# VFD-IV-25-5x7x2_t2.net
KiCad netlist of a schematic drawn in EAGLE
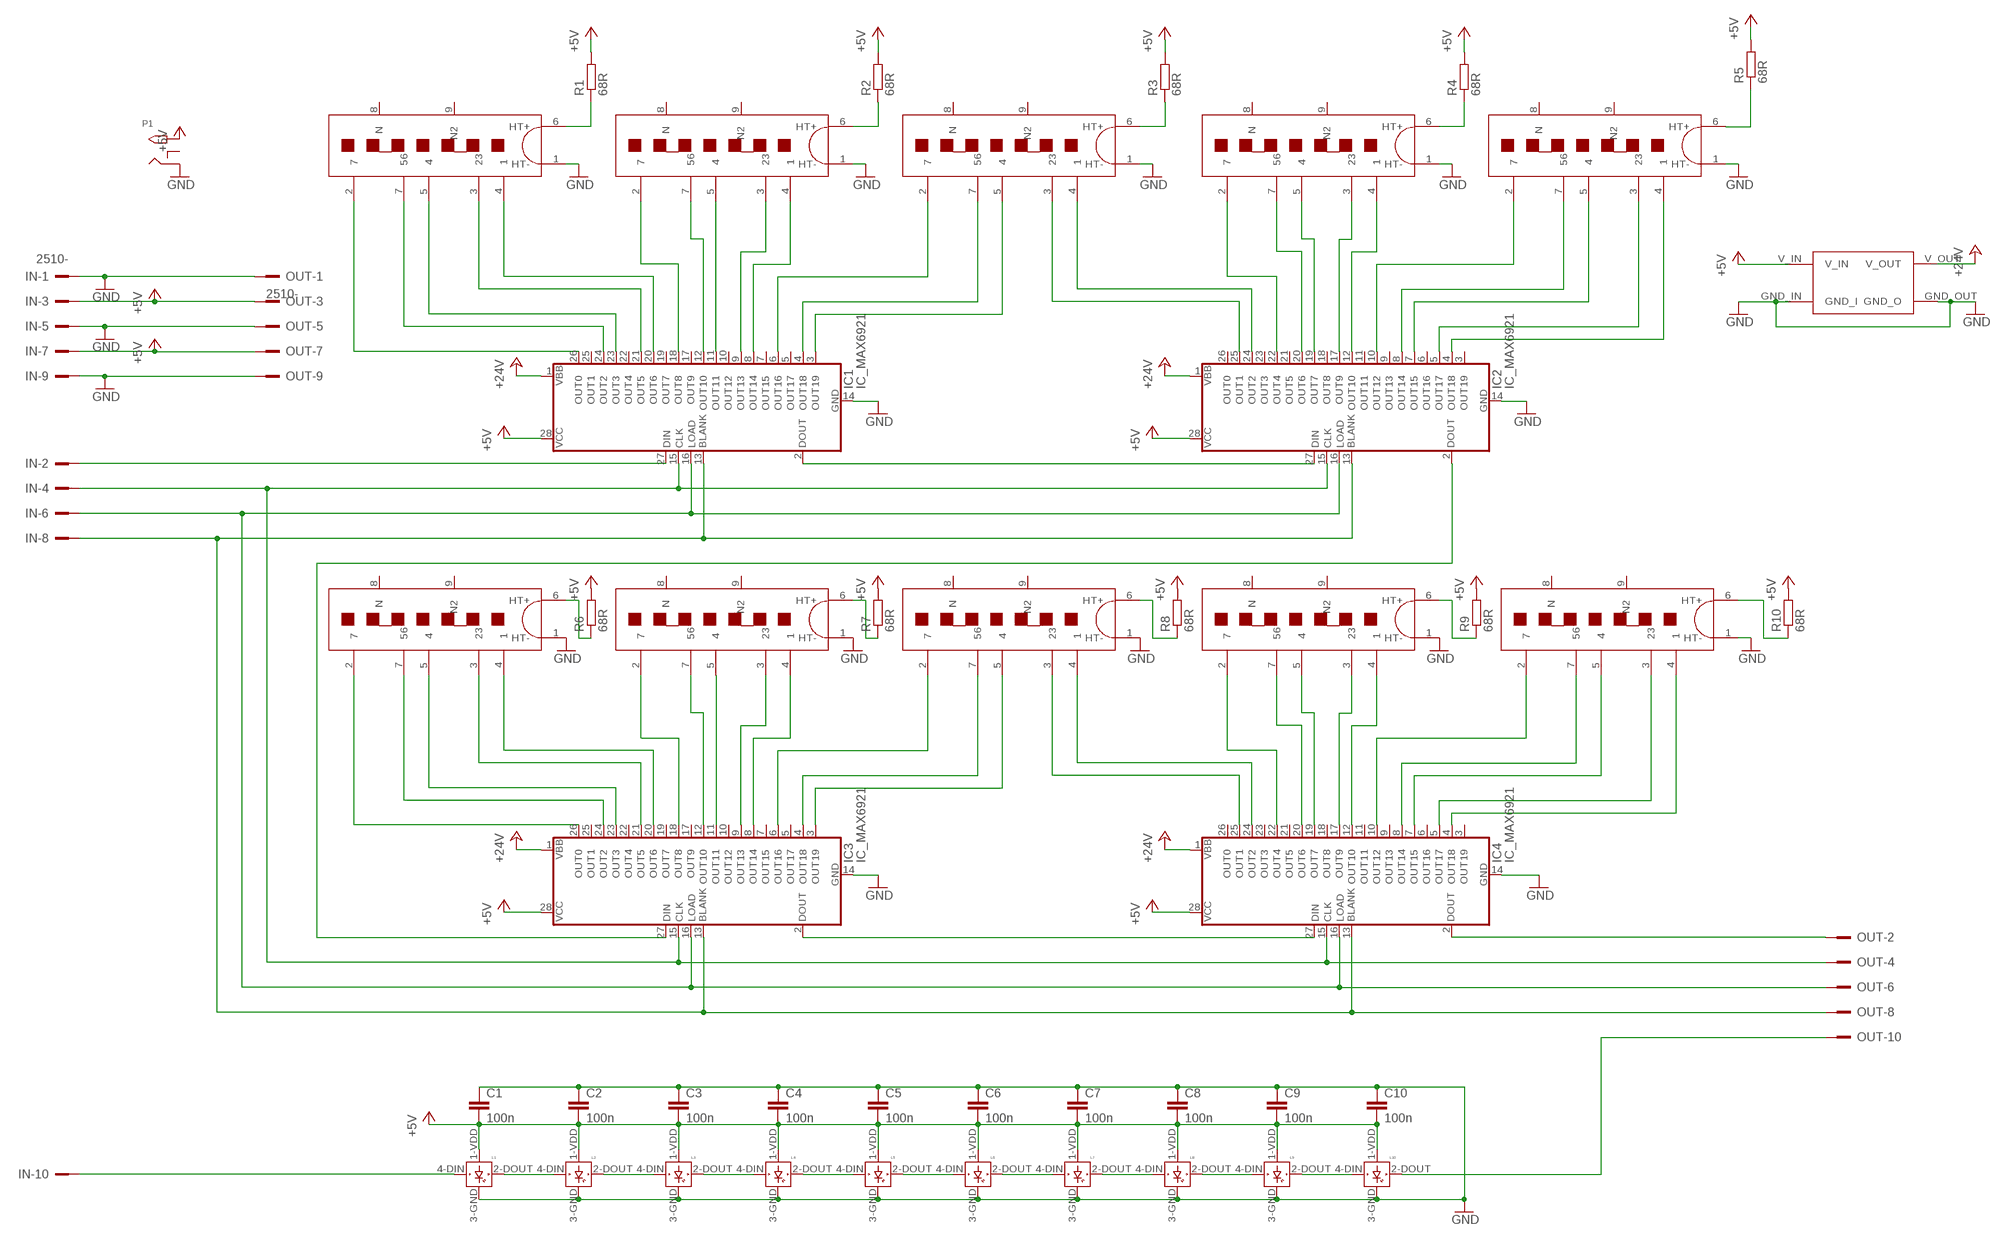
[diagram p0: schematic, sheet 1]

(export (version "E")
  (design (tool "Eeschema 10.0.6"))
  (components
    (comp (ref "1")
      (value "IV-25_DISP_T3")
      (footprint "eagle-import:IV-25")
      (libsource (lib "eagle-import") (part "IV-25_DISP_T3"))
    )
    (comp (ref "2")
      (value "IV-25_DISP_T3")
      (footprint "eagle-import:IV-25")
      (libsource (lib "eagle-import") (part "IV-25_DISP_T3"))
    )
    (comp (ref "3")
      (value "IV-25_DISP_T3")
      (footprint "eagle-import:IV-25")
      (libsource (lib "eagle-import") (part "IV-25_DISP_T3"))
    )
    (comp (ref "4")
      (value "IV-25_DISP_T3")
      (footprint "eagle-import:IV-25")
      (libsource (lib "eagle-import") (part "IV-25_DISP_T3"))
    )
    (comp (ref "5")
      (value "IV-25_DISP_T3")
      (footprint "eagle-import:IV-25")
      (libsource (lib "eagle-import") (part "IV-25_DISP_T3"))
    )
    (comp (ref "6")
      (value "IV-25_DISP_T3")
      (footprint "eagle-import:IV-25")
      (libsource (lib "eagle-import") (part "IV-25_DISP_T3"))
    )
    (comp (ref "7")
      (value "IV-25_DISP_T3")
      (footprint "eagle-import:IV-25")
      (libsource (lib "eagle-import") (part "IV-25_DISP_T3"))
    )
    (comp (ref "8")
      (value "IV-25_DISP_T3")
      (footprint "eagle-import:IV-25")
      (libsource (lib "eagle-import") (part "IV-25_DISP_T3"))
    )
    (comp (ref "9")
      (value "IV-25_DISP_T3")
      (footprint "eagle-import:IV-25")
      (libsource (lib "eagle-import") (part "IV-25_DISP_T3"))
    )
    (comp (ref "10")
      (value "IV-25_DISP_T3")
      (footprint "eagle-import:IV-25")
      (libsource (lib "eagle-import") (part "IV-25_DISP_T3"))
    )
    (comp (ref "C1")
      (value "100n")
      (footprint "eagle-import:C050-025X075")
      (libsource (lib "eagle-import") (part "C-EU050-025X075"))
    )
    (comp (ref "C2")
      (value "100n")
      (footprint "eagle-import:C050-025X075")
      (libsource (lib "eagle-import") (part "C-EU050-025X075"))
    )
    (comp (ref "C3")
      (value "100n")
      (footprint "eagle-import:C050-025X075")
      (libsource (lib "eagle-import") (part "C-EU050-025X075"))
    )
    (comp (ref "C4")
      (value "100n")
      (footprint "eagle-import:C050-025X075")
      (libsource (lib "eagle-import") (part "C-EU050-025X075"))
    )
    (comp (ref "C5")
      (value "100n")
      (footprint "eagle-import:C050-025X075")
      (libsource (lib "eagle-import") (part "C-EU050-025X075"))
    )
    (comp (ref "C6")
      (value "100n")
      (footprint "eagle-import:C050-025X075")
      (libsource (lib "eagle-import") (part "C-EU050-025X075"))
    )
    (comp (ref "C7")
      (value "100n")
      (footprint "eagle-import:C050-025X075")
      (libsource (lib "eagle-import") (part "C-EU050-025X075"))
    )
    (comp (ref "C8")
      (value "100n")
      (footprint "eagle-import:C050-025X075")
      (libsource (lib "eagle-import") (part "C-EU050-025X075"))
    )
    (comp (ref "C9")
      (value "100n")
      (footprint "eagle-import:C050-025X075")
      (libsource (lib "eagle-import") (part "C-EU050-025X075"))
    )
    (comp (ref "C10")
      (value "100n")
      (footprint "eagle-import:C050-025X075")
      (libsource (lib "eagle-import") (part "C-EU050-025X075"))
    )
    (comp (ref "IC1")
      (value "IC_MAX6921")
      (footprint "eagle-import:S28")
      (libsource (lib "eagle-import") (part "IC_MAX6921"))
    )
    (comp (ref "IC2")
      (value "IC_MAX6921")
      (footprint "eagle-import:S28")
      (libsource (lib "eagle-import") (part "IC_MAX6921"))
    )
    (comp (ref "IC3")
      (value "IC_MAX6921")
      (footprint "eagle-import:S28")
      (libsource (lib "eagle-import") (part "IC_MAX6921"))
    )
    (comp (ref "IC4")
      (value "IC_MAX6921")
      (footprint "eagle-import:S28")
      (libsource (lib "eagle-import") (part "IC_MAX6921"))
    )
    (comp (ref "IN")
      (value "2510-")
      (footprint "eagle-import:PAK100_2500-10")
      (fields (field (name "MF") "3M") (field (name "MPN") "2510-6002UB"))
      (libsource (lib "eagle-import") (part "2510-"))
    )
    (comp (ref "L1")
      (value "WS2812B")
      (footprint "eagle-import:WS2812B")
      (libsource (lib "eagle-import") (part "WS2812B"))
    )
    (comp (ref "L2")
      (value "WS2812B")
      (footprint "eagle-import:WS2812B")
      (libsource (lib "eagle-import") (part "WS2812B"))
    )
    (comp (ref "L3")
      (value "WS2812B")
      (footprint "eagle-import:WS2812B")
      (libsource (lib "eagle-import") (part "WS2812B"))
    )
    (comp (ref "L4")
      (value "WS2812B")
      (footprint "eagle-import:WS2812B")
      (libsource (lib "eagle-import") (part "WS2812B"))
    )
    (comp (ref "L5")
      (value "WS2812B")
      (footprint "eagle-import:WS2812B")
      (libsource (lib "eagle-import") (part "WS2812B"))
    )
    (comp (ref "L6")
      (value "WS2812B")
      (footprint "eagle-import:WS2812B")
      (libsource (lib "eagle-import") (part "WS2812B"))
    )
    (comp (ref "L7")
      (value "WS2812B")
      (footprint "eagle-import:WS2812B")
      (libsource (lib "eagle-import") (part "WS2812B"))
    )
    (comp (ref "L8")
      (value "WS2812B")
      (footprint "eagle-import:WS2812B")
      (libsource (lib "eagle-import") (part "WS2812B"))
    )
    (comp (ref "L9")
      (value "WS2812B")
      (footprint "eagle-import:WS2812B")
      (libsource (lib "eagle-import") (part "WS2812B"))
    )
    (comp (ref "L10")
      (value "WS2812B")
      (footprint "eagle-import:WS2812B")
      (libsource (lib "eagle-import") (part "WS2812B"))
    )
    (comp (ref "OUT")
      (value "2510-")
      (footprint "eagle-import:PAK100_2500-10")
      (fields (field (name "MF") "3M") (field (name "MPN") "2510-6002UB"))
      (libsource (lib "eagle-import") (part "2510-"))
    )
    (comp (ref "P1")
      (value "2.1MMJACKTHM")
      (footprint "eagle-import:PJ-102A")
      (libsource (lib "eagle-import") (part "2.1MMJACKTHM"))
    )
    (comp (ref "R1")
      (value "68R")
      (footprint "eagle-import:0207_10")
      (libsource (lib "eagle-import") (part "R-EU_0207/10"))
    )
    (comp (ref "R2")
      (value "68R")
      (footprint "eagle-import:0207_10")
      (libsource (lib "eagle-import") (part "R-EU_0207/10"))
    )
    (comp (ref "R3")
      (value "68R")
      (footprint "eagle-import:0207_10")
      (libsource (lib "eagle-import") (part "R-EU_0207/10"))
    )
    (comp (ref "R4")
      (value "68R")
      (footprint "eagle-import:0207_10")
      (libsource (lib "eagle-import") (part "R-EU_0207/10"))
    )
    (comp (ref "R5")
      (value "68R")
      (footprint "eagle-import:0207_10")
      (libsource (lib "eagle-import") (part "R-EU_0207/10"))
    )
    (comp (ref "R6")
      (value "68R")
      (footprint "eagle-import:0207_10")
      (libsource (lib "eagle-import") (part "R-EU_0207/10"))
    )
    (comp (ref "R7")
      (value "68R")
      (footprint "eagle-import:0207_10")
      (libsource (lib "eagle-import") (part "R-EU_0207/10"))
    )
    (comp (ref "R8")
      (value "68R")
      (footprint "eagle-import:0207_10")
      (libsource (lib "eagle-import") (part "R-EU_0207/10"))
    )
    (comp (ref "R9")
      (value "68R")
      (footprint "eagle-import:0207_10")
      (libsource (lib "eagle-import") (part "R-EU_0207/10"))
    )
    (comp (ref "R10")
      (value "68R")
      (footprint "eagle-import:0207_10")
      (libsource (lib "eagle-import") (part "R-EU_0207/10"))
    )
    (comp (ref "U$11")
      (value "STEP_UP_MODULE")
      (footprint "eagle-import:STEP_UP_MODULE")
      (libsource (lib "eagle-import") (part "STEP_UP_MODULE"))
    )
  )
  (nets
    (net (code "1") (name "+5V") (class "Default")
      (node (ref "C1") (pin "2") (pinfunction "2_2") (pintype "passive"))
      (node (ref "C10") (pin "2") (pinfunction "2_2") (pintype "passive"))
      (node (ref "C2") (pin "2") (pinfunction "2_2") (pintype "passive"))
      (node (ref "C3") (pin "2") (pinfunction "2_2") (pintype "passive"))
      (node (ref "C4") (pin "2") (pinfunction "2_2") (pintype "passive"))
      (node (ref "C5") (pin "2") (pinfunction "2_2") (pintype "passive"))
      (node (ref "C6") (pin "2") (pinfunction "2_2") (pintype "passive"))
      (node (ref "C7") (pin "2") (pinfunction "2_2") (pintype "passive"))
      (node (ref "C8") (pin "2") (pinfunction "2_2") (pintype "passive"))
      (node (ref "C9") (pin "2") (pinfunction "2_2") (pintype "passive"))
      (node (ref "IC1") (pin "28") (pinfunction "VCC_28") (pintype "power_in"))
      (node (ref "IC2") (pin "28") (pinfunction "VCC_28") (pintype "power_in"))
      (node (ref "IC3") (pin "28") (pinfunction "VCC_28") (pintype "power_in"))
      (node (ref "IC4") (pin "28") (pinfunction "VCC_28") (pintype "power_in"))
      (node (ref "IN") (pin "3") (pinfunction "KL_3") (pintype "passive"))
      (node (ref "IN") (pin "7") (pinfunction "KL_7") (pintype "passive"))
      (node (ref "L1") (pin "1-VDD") (pinfunction "VDD_1-VDD") (pintype "bidirectional"))
      (node (ref "L10") (pin "1-VDD") (pinfunction "VDD_1-VDD") (pintype "bidirectional"))
      (node (ref "L2") (pin "1-VDD") (pinfunction "VDD_1-VDD") (pintype "bidirectional"))
      (node (ref "L3") (pin "1-VDD") (pinfunction "VDD_1-VDD") (pintype "bidirectional"))
      (node (ref "L4") (pin "1-VDD") (pinfunction "VDD_1-VDD") (pintype "bidirectional"))
      (node (ref "L5") (pin "1-VDD") (pinfunction "VDD_1-VDD") (pintype "bidirectional"))
      (node (ref "L6") (pin "1-VDD") (pinfunction "VDD_1-VDD") (pintype "bidirectional"))
      (node (ref "L7") (pin "1-VDD") (pinfunction "VDD_1-VDD") (pintype "bidirectional"))
      (node (ref "L8") (pin "1-VDD") (pinfunction "VDD_1-VDD") (pintype "bidirectional"))
      (node (ref "L9") (pin "1-VDD") (pinfunction "VDD_1-VDD") (pintype "bidirectional"))
      (node (ref "OUT") (pin "3") (pinfunction "KL_3") (pintype "passive"))
      (node (ref "OUT") (pin "7") (pinfunction "KL_7") (pintype "passive"))
      (node (ref "P1") (pin "TIP") (pinfunction "TIP_TIP") (pintype "bidirectional"))
      (node (ref "R1") (pin "2") (pinfunction "2_2") (pintype "passive"))
      (node (ref "R10") (pin "2") (pinfunction "2_2") (pintype "passive"))
      (node (ref "R2") (pin "2") (pinfunction "2_2") (pintype "passive"))
      (node (ref "R3") (pin "2") (pinfunction "2_2") (pintype "passive"))
      (node (ref "R4") (pin "2") (pinfunction "2_2") (pintype "passive"))
      (node (ref "R5") (pin "2") (pinfunction "2_2") (pintype "passive"))
      (node (ref "R6") (pin "2") (pinfunction "2_2") (pintype "passive"))
      (node (ref "R7") (pin "2") (pinfunction "2_2") (pintype "passive"))
      (node (ref "R8") (pin "2") (pinfunction "2_2") (pintype "passive"))
      (node (ref "R9") (pin "2") (pinfunction "2_2") (pintype "passive"))
      (node (ref "U$11") (pin "V_IN") (pinfunction "V_IN_V_IN") (pintype "power_in"))
    )
    (net (code "2") (name "+24V") (class "Default")
      (node (ref "IC1") (pin "1") (pinfunction "VBB_1") (pintype "power_in"))
      (node (ref "IC2") (pin "1") (pinfunction "VBB_1") (pintype "power_in"))
      (node (ref "IC3") (pin "1") (pinfunction "VBB_1") (pintype "power_in"))
      (node (ref "IC4") (pin "1") (pinfunction "VBB_1") (pintype "power_in"))
      (node (ref "U$11") (pin "V_OUT") (pinfunction "V_OUT_V_OUT") (pintype "power_in"))
    )
    (net (code "3") (name "GND") (class "Default")
      (node (ref "1") (pin "1") (pinfunction "HT-_1") (pintype "bidirectional"))
      (node (ref "10") (pin "1") (pinfunction "HT-_1") (pintype "bidirectional"))
      (node (ref "2") (pin "1") (pinfunction "HT-_1") (pintype "bidirectional"))
      (node (ref "3") (pin "1") (pinfunction "HT-_1") (pintype "bidirectional"))
      (node (ref "4") (pin "1") (pinfunction "HT-_1") (pintype "bidirectional"))
      (node (ref "5") (pin "1") (pinfunction "HT-_1") (pintype "bidirectional"))
      (node (ref "6") (pin "1") (pinfunction "HT-_1") (pintype "bidirectional"))
      (node (ref "7") (pin "1") (pinfunction "HT-_1") (pintype "bidirectional"))
      (node (ref "8") (pin "1") (pinfunction "HT-_1") (pintype "bidirectional"))
      (node (ref "9") (pin "1") (pinfunction "HT-_1") (pintype "bidirectional"))
      (node (ref "C1") (pin "1") (pinfunction "1_1") (pintype "passive"))
      (node (ref "C10") (pin "1") (pinfunction "1_1") (pintype "passive"))
      (node (ref "C2") (pin "1") (pinfunction "1_1") (pintype "passive"))
      (node (ref "C3") (pin "1") (pinfunction "1_1") (pintype "passive"))
      (node (ref "C4") (pin "1") (pinfunction "1_1") (pintype "passive"))
      (node (ref "C5") (pin "1") (pinfunction "1_1") (pintype "passive"))
      (node (ref "C6") (pin "1") (pinfunction "1_1") (pintype "passive"))
      (node (ref "C7") (pin "1") (pinfunction "1_1") (pintype "passive"))
      (node (ref "C8") (pin "1") (pinfunction "1_1") (pintype "passive"))
      (node (ref "C9") (pin "1") (pinfunction "1_1") (pintype "passive"))
      (node (ref "IC1") (pin "14") (pinfunction "GND_14") (pintype "power_in"))
      (node (ref "IC2") (pin "14") (pinfunction "GND_14") (pintype "power_in"))
      (node (ref "IC3") (pin "14") (pinfunction "GND_14") (pintype "power_in"))
      (node (ref "IC4") (pin "14") (pinfunction "GND_14") (pintype "power_in"))
      (node (ref "IN") (pin "1") (pinfunction "KL_1") (pintype "passive"))
      (node (ref "IN") (pin "5") (pinfunction "KL_5") (pintype "passive"))
      (node (ref "IN") (pin "9") (pinfunction "KL_9") (pintype "passive"))
      (node (ref "L1") (pin "3-GND") (pinfunction "GND_3-GND") (pintype "bidirectional"))
      (node (ref "L10") (pin "3-GND") (pinfunction "GND_3-GND") (pintype "bidirectional"))
      (node (ref "L2") (pin "3-GND") (pinfunction "GND_3-GND") (pintype "bidirectional"))
      (node (ref "L3") (pin "3-GND") (pinfunction "GND_3-GND") (pintype "bidirectional"))
      (node (ref "L4") (pin "3-GND") (pinfunction "GND_3-GND") (pintype "bidirectional"))
      (node (ref "L5") (pin "3-GND") (pinfunction "GND_3-GND") (pintype "bidirectional"))
      (node (ref "L6") (pin "3-GND") (pinfunction "GND_3-GND") (pintype "bidirectional"))
      (node (ref "L7") (pin "3-GND") (pinfunction "GND_3-GND") (pintype "bidirectional"))
      (node (ref "L8") (pin "3-GND") (pinfunction "GND_3-GND") (pintype "bidirectional"))
      (node (ref "L9") (pin "3-GND") (pinfunction "GND_3-GND") (pintype "bidirectional"))
      (node (ref "OUT") (pin "1") (pinfunction "KL_1") (pintype "passive"))
      (node (ref "OUT") (pin "5") (pinfunction "KL_5") (pintype "passive"))
      (node (ref "OUT") (pin "9") (pinfunction "KL_9") (pintype "passive"))
      (node (ref "P1") (pin "RING") (pinfunction "RING_RING") (pintype "bidirectional"))
      (node (ref "U$11") (pin "GND_IN") (pinfunction "GND_I_GND_IN") (pintype "power_in"))
      (node (ref "U$11") (pin "GND_OUT") (pinfunction "GND_O_GND_OUT") (pintype "power_in"))
    )
    (net (code "4") (name "Net-(1-1)") (class "Default")
      (node (ref "1") (pin "4") (pinfunction "1_4") (pintype "input"))
      (node (ref "IC1") (pin "20") (pinfunction "OUT6_20") (pintype "output"))
    )
    (net (code "5") (name "Net-(1-4)") (class "Default")
      (node (ref "1") (pin "5") (pinfunction "4_5") (pintype "input"))
      (node (ref "IC1") (pin "23") (pinfunction "OUT3_23") (pintype "output"))
    )
    (net (code "6") (name "Net-(1-7)") (class "Default")
      (node (ref "1") (pin "2") (pinfunction "7_2") (pintype "input"))
      (node (ref "IC1") (pin "26") (pinfunction "OUT0_26") (pintype "output"))
    )
    (net (code "7") (name "Net-(1-23)") (class "Default")
      (node (ref "1") (pin "3") (pinfunction "23_3") (pintype "input"))
      (node (ref "IC1") (pin "21") (pinfunction "OUT5_21") (pintype "output"))
    )
    (net (code "8") (name "Net-(1-56)") (class "Default")
      (node (ref "1") (pin "7") (pinfunction "56_7") (pintype "input"))
      (node (ref "IC1") (pin "24") (pinfunction "OUT2_24") (pintype "output"))
    )
    (net (code "9") (name "Net-(1-HT+)") (class "Default")
      (node (ref "1") (pin "6") (pinfunction "HT+_6") (pintype "bidirectional"))
      (node (ref "R1") (pin "1") (pinfunction "1_1") (pintype "passive"))
    )
    (net (code "10") (name "Net-(2-1)") (class "Default")
      (node (ref "2") (pin "4") (pinfunction "1_4") (pintype "input"))
      (node (ref "IC1") (pin "8") (pinfunction "OUT14_8") (pintype "output"))
    )
    (net (code "11") (name "Net-(2-4)") (class "Default")
      (node (ref "2") (pin "5") (pinfunction "4_5") (pintype "input"))
      (node (ref "IC1") (pin "11") (pinfunction "OUT11_11") (pintype "output"))
    )
    (net (code "12") (name "Net-(2-7)") (class "Default")
      (node (ref "2") (pin "2") (pinfunction "7_2") (pintype "input"))
      (node (ref "IC1") (pin "18") (pinfunction "OUT8_18") (pintype "output"))
    )
    (net (code "13") (name "Net-(2-23)") (class "Default")
      (node (ref "2") (pin "3") (pinfunction "23_3") (pintype "input"))
      (node (ref "IC1") (pin "9") (pinfunction "OUT13_9") (pintype "output"))
    )
    (net (code "14") (name "Net-(2-56)") (class "Default")
      (node (ref "2") (pin "7") (pinfunction "56_7") (pintype "input"))
      (node (ref "IC1") (pin "12") (pinfunction "OUT10_12") (pintype "output"))
    )
    (net (code "15") (name "Net-(2-HT+)") (class "Default")
      (node (ref "2") (pin "6") (pinfunction "HT+_6") (pintype "bidirectional"))
      (node (ref "R2") (pin "1") (pinfunction "1_1") (pintype "passive"))
    )
    (net (code "16") (name "Net-(3-1)") (class "Default")
      (node (ref "3") (pin "4") (pinfunction "1_4") (pintype "input"))
      (node (ref "IC2") (pin "24") (pinfunction "OUT2_24") (pintype "output"))
    )
    (net (code "17") (name "Net-(3-4)") (class "Default")
      (node (ref "3") (pin "5") (pinfunction "4_5") (pintype "input"))
      (node (ref "IC1") (pin "3") (pinfunction "OUT19_3") (pintype "output"))
    )
    (net (code "18") (name "Net-(3-7)") (class "Default")
      (node (ref "3") (pin "2") (pinfunction "7_2") (pintype "input"))
      (node (ref "IC1") (pin "6") (pinfunction "OUT16_6") (pintype "output"))
    )
    (net (code "19") (name "Net-(3-23)") (class "Default")
      (node (ref "3") (pin "3") (pinfunction "23_3") (pintype "input"))
      (node (ref "IC2") (pin "25") (pinfunction "OUT1_25") (pintype "output"))
    )
    (net (code "20") (name "Net-(3-56)") (class "Default")
      (node (ref "3") (pin "7") (pinfunction "56_7") (pintype "input"))
      (node (ref "IC1") (pin "4") (pinfunction "OUT18_4") (pintype "output"))
    )
    (net (code "21") (name "Net-(3-HT+)") (class "Default")
      (node (ref "3") (pin "6") (pinfunction "HT+_6") (pintype "bidirectional"))
      (node (ref "R3") (pin "1") (pinfunction "1_1") (pintype "passive"))
    )
    (net (code "22") (name "Net-(4-1)") (class "Default")
      (node (ref "4") (pin "4") (pinfunction "1_4") (pintype "input"))
      (node (ref "IC2") (pin "12") (pinfunction "OUT10_12") (pintype "output"))
    )
    (net (code "23") (name "Net-(4-4)") (class "Default")
      (node (ref "4") (pin "5") (pinfunction "4_5") (pintype "input"))
      (node (ref "IC2") (pin "19") (pinfunction "OUT7_19") (pintype "output"))
    )
    (net (code "24") (name "Net-(4-7)") (class "Default")
      (node (ref "4") (pin "2") (pinfunction "7_2") (pintype "input"))
      (node (ref "IC2") (pin "22") (pinfunction "OUT4_22") (pintype "output"))
    )
    (net (code "25") (name "Net-(4-23)") (class "Default")
      (node (ref "4") (pin "3") (pinfunction "23_3") (pintype "input"))
      (node (ref "IC2") (pin "17") (pinfunction "OUT9_17") (pintype "output"))
    )
    (net (code "26") (name "Net-(4-56)") (class "Default")
      (node (ref "4") (pin "7") (pinfunction "56_7") (pintype "input"))
      (node (ref "IC2") (pin "20") (pinfunction "OUT6_20") (pintype "output"))
    )
    (net (code "27") (name "Net-(4-HT+)") (class "Default")
      (node (ref "4") (pin "6") (pinfunction "HT+_6") (pintype "bidirectional"))
      (node (ref "R4") (pin "1") (pinfunction "1_1") (pintype "passive"))
    )
    (net (code "28") (name "Net-(5-1)") (class "Default")
      (node (ref "5") (pin "4") (pinfunction "1_4") (pintype "input"))
      (node (ref "IC2") (pin "4") (pinfunction "OUT18_4") (pintype "output"))
    )
    (net (code "29") (name "Net-(5-4)") (class "Default")
      (node (ref "5") (pin "5") (pinfunction "4_5") (pintype "input"))
      (node (ref "IC2") (pin "7") (pinfunction "OUT15_7") (pintype "output"))
    )
    (net (code "30") (name "Net-(5-7)") (class "Default")
      (node (ref "5") (pin "2") (pinfunction "7_2") (pintype "input"))
      (node (ref "IC2") (pin "10") (pinfunction "OUT12_10") (pintype "output"))
    )
    (net (code "31") (name "Net-(5-23)") (class "Default")
      (node (ref "5") (pin "3") (pinfunction "23_3") (pintype "input"))
      (node (ref "IC2") (pin "5") (pinfunction "OUT17_5") (pintype "output"))
    )
    (net (code "32") (name "Net-(5-56)") (class "Default")
      (node (ref "5") (pin "7") (pinfunction "56_7") (pintype "input"))
      (node (ref "IC2") (pin "8") (pinfunction "OUT14_8") (pintype "output"))
    )
    (net (code "33") (name "Net-(5-HT+)") (class "Default")
      (node (ref "5") (pin "6") (pinfunction "HT+_6") (pintype "bidirectional"))
      (node (ref "R5") (pin "1") (pinfunction "1_1") (pintype "passive"))
    )
    (net (code "34") (name "Net-(6-1)") (class "Default")
      (node (ref "6") (pin "4") (pinfunction "1_4") (pintype "input"))
      (node (ref "IC3") (pin "20") (pinfunction "OUT6_20") (pintype "output"))
    )
    (net (code "35") (name "Net-(6-4)") (class "Default")
      (node (ref "6") (pin "5") (pinfunction "4_5") (pintype "input"))
      (node (ref "IC3") (pin "23") (pinfunction "OUT3_23") (pintype "output"))
    )
    (net (code "36") (name "Net-(6-7)") (class "Default")
      (node (ref "6") (pin "2") (pinfunction "7_2") (pintype "input"))
      (node (ref "IC3") (pin "26") (pinfunction "OUT0_26") (pintype "output"))
    )
    (net (code "37") (name "Net-(6-23)") (class "Default")
      (node (ref "6") (pin "3") (pinfunction "23_3") (pintype "input"))
      (node (ref "IC3") (pin "21") (pinfunction "OUT5_21") (pintype "output"))
    )
    (net (code "38") (name "Net-(6-56)") (class "Default")
      (node (ref "6") (pin "7") (pinfunction "56_7") (pintype "input"))
      (node (ref "IC3") (pin "24") (pinfunction "OUT2_24") (pintype "output"))
    )
    (net (code "39") (name "Net-(6-HT+)") (class "Default")
      (node (ref "6") (pin "6") (pinfunction "HT+_6") (pintype "bidirectional"))
      (node (ref "R6") (pin "1") (pinfunction "1_1") (pintype "passive"))
    )
    (net (code "40") (name "Net-(7-1)") (class "Default")
      (node (ref "7") (pin "4") (pinfunction "1_4") (pintype "input"))
      (node (ref "IC3") (pin "8") (pinfunction "OUT14_8") (pintype "output"))
    )
    (net (code "41") (name "Net-(7-4)") (class "Default")
      (node (ref "7") (pin "5") (pinfunction "4_5") (pintype "input"))
      (node (ref "IC3") (pin "11") (pinfunction "OUT11_11") (pintype "output"))
    )
    (net (code "42") (name "Net-(7-7)") (class "Default")
      (node (ref "7") (pin "2") (pinfunction "7_2") (pintype "input"))
      (node (ref "IC3") (pin "18") (pinfunction "OUT8_18") (pintype "output"))
    )
    (net (code "43") (name "Net-(7-23)") (class "Default")
      (node (ref "7") (pin "3") (pinfunction "23_3") (pintype "input"))
      (node (ref "IC3") (pin "9") (pinfunction "OUT13_9") (pintype "output"))
    )
    (net (code "44") (name "Net-(7-56)") (class "Default")
      (node (ref "7") (pin "7") (pinfunction "56_7") (pintype "input"))
      (node (ref "IC3") (pin "12") (pinfunction "OUT10_12") (pintype "output"))
    )
    (net (code "45") (name "Net-(7-HT+)") (class "Default")
      (node (ref "7") (pin "6") (pinfunction "HT+_6") (pintype "bidirectional"))
      (node (ref "R7") (pin "1") (pinfunction "1_1") (pintype "passive"))
    )
    (net (code "46") (name "Net-(8-1)") (class "Default")
      (node (ref "8") (pin "4") (pinfunction "1_4") (pintype "input"))
      (node (ref "IC4") (pin "24") (pinfunction "OUT2_24") (pintype "output"))
    )
    (net (code "47") (name "Net-(8-4)") (class "Default")
      (node (ref "8") (pin "5") (pinfunction "4_5") (pintype "input"))
      (node (ref "IC3") (pin "3") (pinfunction "OUT19_3") (pintype "output"))
    )
    (net (code "48") (name "Net-(8-7)") (class "Default")
      (node (ref "8") (pin "2") (pinfunction "7_2") (pintype "input"))
      (node (ref "IC3") (pin "6") (pinfunction "OUT16_6") (pintype "output"))
    )
    (net (code "49") (name "Net-(8-23)") (class "Default")
      (node (ref "8") (pin "3") (pinfunction "23_3") (pintype "input"))
      (node (ref "IC4") (pin "25") (pinfunction "OUT1_25") (pintype "output"))
    )
    (net (code "50") (name "Net-(8-56)") (class "Default")
      (node (ref "8") (pin "7") (pinfunction "56_7") (pintype "input"))
      (node (ref "IC3") (pin "4") (pinfunction "OUT18_4") (pintype "output"))
    )
    (net (code "51") (name "Net-(8-HT+)") (class "Default")
      (node (ref "8") (pin "6") (pinfunction "HT+_6") (pintype "bidirectional"))
      (node (ref "R8") (pin "1") (pinfunction "1_1") (pintype "passive"))
    )
    (net (code "52") (name "Net-(9-1)") (class "Default")
      (node (ref "9") (pin "4") (pinfunction "1_4") (pintype "input"))
      (node (ref "IC4") (pin "12") (pinfunction "OUT10_12") (pintype "output"))
    )
    (net (code "53") (name "Net-(9-4)") (class "Default")
      (node (ref "9") (pin "5") (pinfunction "4_5") (pintype "input"))
      (node (ref "IC4") (pin "19") (pinfunction "OUT7_19") (pintype "output"))
    )
    (net (code "54") (name "Net-(9-7)") (class "Default")
      (node (ref "9") (pin "2") (pinfunction "7_2") (pintype "input"))
      (node (ref "IC4") (pin "22") (pinfunction "OUT4_22") (pintype "output"))
    )
    (net (code "55") (name "Net-(9-23)") (class "Default")
      (node (ref "9") (pin "3") (pinfunction "23_3") (pintype "input"))
      (node (ref "IC4") (pin "17") (pinfunction "OUT9_17") (pintype "output"))
    )
    (net (code "56") (name "Net-(9-56)") (class "Default")
      (node (ref "9") (pin "7") (pinfunction "56_7") (pintype "input"))
      (node (ref "IC4") (pin "20") (pinfunction "OUT6_20") (pintype "output"))
    )
    (net (code "57") (name "Net-(9-HT+)") (class "Default")
      (node (ref "9") (pin "6") (pinfunction "HT+_6") (pintype "bidirectional"))
      (node (ref "R9") (pin "1") (pinfunction "1_1") (pintype "passive"))
    )
    (net (code "58") (name "Net-(10-1)") (class "Default")
      (node (ref "10") (pin "4") (pinfunction "1_4") (pintype "input"))
      (node (ref "IC4") (pin "4") (pinfunction "OUT18_4") (pintype "output"))
    )
    (net (code "59") (name "Net-(10-4)") (class "Default")
      (node (ref "10") (pin "5") (pinfunction "4_5") (pintype "input"))
      (node (ref "IC4") (pin "7") (pinfunction "OUT15_7") (pintype "output"))
    )
    (net (code "60") (name "Net-(10-7)") (class "Default")
      (node (ref "10") (pin "2") (pinfunction "7_2") (pintype "input"))
      (node (ref "IC4") (pin "10") (pinfunction "OUT12_10") (pintype "output"))
    )
    (net (code "61") (name "Net-(10-23)") (class "Default")
      (node (ref "10") (pin "3") (pinfunction "23_3") (pintype "input"))
      (node (ref "IC4") (pin "5") (pinfunction "OUT17_5") (pintype "output"))
    )
    (net (code "62") (name "Net-(10-56)") (class "Default")
      (node (ref "10") (pin "7") (pinfunction "56_7") (pintype "input"))
      (node (ref "IC4") (pin "8") (pinfunction "OUT14_8") (pintype "output"))
    )
    (net (code "63") (name "Net-(10-HT+)") (class "Default")
      (node (ref "10") (pin "6") (pinfunction "HT+_6") (pintype "bidirectional"))
      (node (ref "R10") (pin "1") (pinfunction "1_1") (pintype "passive"))
    )
    (net (code "64") (name "Net-(IC1-BLANK)") (class "Default")
      (node (ref "IC1") (pin "13") (pinfunction "BLANK_13") (pintype "input"))
      (node (ref "IC2") (pin "13") (pinfunction "BLANK_13") (pintype "input"))
      (node (ref "IC3") (pin "13") (pinfunction "BLANK_13") (pintype "input"))
      (node (ref "IC4") (pin "13") (pinfunction "BLANK_13") (pintype "input"))
      (node (ref "IN") (pin "8") (pinfunction "KL_8") (pintype "passive"))
      (node (ref "OUT") (pin "8") (pinfunction "KL_8") (pintype "passive"))
    )
    (net (code "65") (name "Net-(IC1-CLK)") (class "Default")
      (node (ref "IC1") (pin "15") (pinfunction "CLK_15") (pintype "input"))
      (node (ref "IC2") (pin "15") (pinfunction "CLK_15") (pintype "input"))
      (node (ref "IC3") (pin "15") (pinfunction "CLK_15") (pintype "input"))
      (node (ref "IC4") (pin "15") (pinfunction "CLK_15") (pintype "input"))
      (node (ref "IN") (pin "4") (pinfunction "KL_4") (pintype "passive"))
      (node (ref "OUT") (pin "4") (pinfunction "KL_4") (pintype "passive"))
    )
    (net (code "66") (name "Net-(IC1-DIN)") (class "Default")
      (node (ref "IC1") (pin "27") (pinfunction "DIN_27") (pintype "input"))
      (node (ref "IN") (pin "2") (pinfunction "KL_2") (pintype "passive"))
    )
    (net (code "67") (name "Net-(IC1-DOUT)") (class "Default")
      (node (ref "IC1") (pin "2") (pinfunction "DOUT_2") (pintype "output"))
      (node (ref "IC2") (pin "27") (pinfunction "DIN_27") (pintype "input"))
    )
    (net (code "68") (name "Net-(IC1-LOAD)") (class "Default")
      (node (ref "IC1") (pin "16") (pinfunction "LOAD_16") (pintype "input"))
      (node (ref "IC2") (pin "16") (pinfunction "LOAD_16") (pintype "input"))
      (node (ref "IC3") (pin "16") (pinfunction "LOAD_16") (pintype "input"))
      (node (ref "IC4") (pin "16") (pinfunction "LOAD_16") (pintype "input"))
      (node (ref "IN") (pin "6") (pinfunction "KL_6") (pintype "passive"))
      (node (ref "OUT") (pin "6") (pinfunction "KL_6") (pintype "passive"))
    )
    (net (code "69") (name "Net-(IC2-DOUT)") (class "Default")
      (node (ref "IC2") (pin "2") (pinfunction "DOUT_2") (pintype "output"))
      (node (ref "IC3") (pin "27") (pinfunction "DIN_27") (pintype "input"))
    )
    (net (code "70") (name "Net-(IC3-DOUT)") (class "Default")
      (node (ref "IC3") (pin "2") (pinfunction "DOUT_2") (pintype "output"))
      (node (ref "IC4") (pin "27") (pinfunction "DIN_27") (pintype "input"))
    )
    (net (code "71") (name "Net-(IC4-DOUT)") (class "Default")
      (node (ref "IC4") (pin "2") (pinfunction "DOUT_2") (pintype "output"))
      (node (ref "OUT") (pin "2") (pinfunction "KL_2") (pintype "passive"))
    )
    (net (code "72") (name "Net-(INB-KL)") (class "Default")
      (node (ref "IN") (pin "10") (pinfunction "KL_10") (pintype "passive"))
      (node (ref "L1") (pin "4-DIN") (pinfunction "DIN_4-DIN") (pintype "input"))
    )
    (net (code "73") (name "Net-(L1-DOUT)") (class "Default")
      (node (ref "L1") (pin "2-DOUT") (pinfunction "DOUT_2-DOUT") (pintype "output"))
      (node (ref "L2") (pin "4-DIN") (pinfunction "DIN_4-DIN") (pintype "input"))
    )
    (net (code "74") (name "Net-(L2-DOUT)") (class "Default")
      (node (ref "L2") (pin "2-DOUT") (pinfunction "DOUT_2-DOUT") (pintype "output"))
      (node (ref "L3") (pin "4-DIN") (pinfunction "DIN_4-DIN") (pintype "input"))
    )
    (net (code "75") (name "Net-(L3-DOUT)") (class "Default")
      (node (ref "L3") (pin "2-DOUT") (pinfunction "DOUT_2-DOUT") (pintype "output"))
      (node (ref "L4") (pin "4-DIN") (pinfunction "DIN_4-DIN") (pintype "input"))
    )
    (net (code "76") (name "Net-(L4-DOUT)") (class "Default")
      (node (ref "L4") (pin "2-DOUT") (pinfunction "DOUT_2-DOUT") (pintype "output"))
      (node (ref "L5") (pin "4-DIN") (pinfunction "DIN_4-DIN") (pintype "input"))
    )
    (net (code "77") (name "Net-(L5-DOUT)") (class "Default")
      (node (ref "L5") (pin "2-DOUT") (pinfunction "DOUT_2-DOUT") (pintype "output"))
      (node (ref "L6") (pin "4-DIN") (pinfunction "DIN_4-DIN") (pintype "input"))
    )
    (net (code "78") (name "Net-(L6-DOUT)") (class "Default")
      (node (ref "L6") (pin "2-DOUT") (pinfunction "DOUT_2-DOUT") (pintype "output"))
      (node (ref "L7") (pin "4-DIN") (pinfunction "DIN_4-DIN") (pintype "input"))
    )
    (net (code "79") (name "Net-(L7-DOUT)") (class "Default")
      (node (ref "L7") (pin "2-DOUT") (pinfunction "DOUT_2-DOUT") (pintype "output"))
      (node (ref "L8") (pin "4-DIN") (pinfunction "DIN_4-DIN") (pintype "input"))
    )
    (net (code "80") (name "Net-(L8-DOUT)") (class "Default")
      (node (ref "L8") (pin "2-DOUT") (pinfunction "DOUT_2-DOUT") (pintype "output"))
      (node (ref "L9") (pin "4-DIN") (pinfunction "DIN_4-DIN") (pintype "input"))
    )
    (net (code "81") (name "Net-(L10-DIN)") (class "Default")
      (node (ref "L10") (pin "4-DIN") (pinfunction "DIN_4-DIN") (pintype "input"))
      (node (ref "L9") (pin "2-DOUT") (pinfunction "DOUT_2-DOUT") (pintype "output"))
    )
    (net (code "82") (name "Net-(L10-DOUT)") (class "Default")
      (node (ref "L10") (pin "2-DOUT") (pinfunction "DOUT_2-DOUT") (pintype "output"))
      (node (ref "OUT") (pin "10") (pinfunction "KL_10") (pintype "passive"))
    )
    (net (code "83") (name "unconnected-(1-N-Pad8)") (class "Default")
      (node (ref "1") (pin "8") (pinfunction "N_8") (pintype "no_connect"))
    )
    (net (code "84") (name "unconnected-(1-N2-Pad9)") (class "Default")
      (node (ref "1") (pin "9") (pinfunction "N2_9") (pintype "no_connect"))
    )
    (net (code "85") (name "unconnected-(2-N-Pad8)") (class "Default")
      (node (ref "2") (pin "8") (pinfunction "N_8") (pintype "no_connect"))
    )
    (net (code "86") (name "unconnected-(2-N2-Pad9)") (class "Default")
      (node (ref "2") (pin "9") (pinfunction "N2_9") (pintype "no_connect"))
    )
    (net (code "87") (name "unconnected-(3-N-Pad8)") (class "Default")
      (node (ref "3") (pin "8") (pinfunction "N_8") (pintype "no_connect"))
    )
    (net (code "88") (name "unconnected-(3-N2-Pad9)") (class "Default")
      (node (ref "3") (pin "9") (pinfunction "N2_9") (pintype "no_connect"))
    )
    (net (code "89") (name "unconnected-(4-N-Pad8)") (class "Default")
      (node (ref "4") (pin "8") (pinfunction "N_8") (pintype "no_connect"))
    )
    (net (code "90") (name "unconnected-(4-N2-Pad9)") (class "Default")
      (node (ref "4") (pin "9") (pinfunction "N2_9") (pintype "no_connect"))
    )
    (net (code "91") (name "unconnected-(5-N-Pad8)") (class "Default")
      (node (ref "5") (pin "8") (pinfunction "N_8") (pintype "no_connect"))
    )
    (net (code "92") (name "unconnected-(5-N2-Pad9)") (class "Default")
      (node (ref "5") (pin "9") (pinfunction "N2_9") (pintype "no_connect"))
    )
    (net (code "93") (name "unconnected-(6-N-Pad8)") (class "Default")
      (node (ref "6") (pin "8") (pinfunction "N_8") (pintype "no_connect"))
    )
    (net (code "94") (name "unconnected-(6-N2-Pad9)") (class "Default")
      (node (ref "6") (pin "9") (pinfunction "N2_9") (pintype "no_connect"))
    )
    (net (code "95") (name "unconnected-(7-N-Pad8)") (class "Default")
      (node (ref "7") (pin "8") (pinfunction "N_8") (pintype "no_connect"))
    )
    (net (code "96") (name "unconnected-(7-N2-Pad9)") (class "Default")
      (node (ref "7") (pin "9") (pinfunction "N2_9") (pintype "no_connect"))
    )
    (net (code "97") (name "unconnected-(8-N-Pad8)") (class "Default")
      (node (ref "8") (pin "8") (pinfunction "N_8") (pintype "no_connect"))
    )
    (net (code "98") (name "unconnected-(8-N2-Pad9)") (class "Default")
      (node (ref "8") (pin "9") (pinfunction "N2_9") (pintype "no_connect"))
    )
    (net (code "99") (name "unconnected-(9-N-Pad8)") (class "Default")
      (node (ref "9") (pin "8") (pinfunction "N_8") (pintype "no_connect"))
    )
    (net (code "100") (name "unconnected-(9-N2-Pad9)") (class "Default")
      (node (ref "9") (pin "9") (pinfunction "N2_9") (pintype "no_connect"))
    )
    (net (code "101") (name "unconnected-(10-N-Pad8)") (class "Default")
      (node (ref "10") (pin "8") (pinfunction "N_8") (pintype "no_connect"))
    )
    (net (code "102") (name "unconnected-(10-N2-Pad9)") (class "Default")
      (node (ref "10") (pin "9") (pinfunction "N2_9") (pintype "no_connect"))
    )
    (net (code "103") (name "unconnected-(IC1-OUT1-Pad25)") (class "Default")
      (node (ref "IC1") (pin "25") (pinfunction "OUT1_25") (pintype "output"))
    )
    (net (code "104") (name "unconnected-(IC1-OUT4-Pad22)") (class "Default")
      (node (ref "IC1") (pin "22") (pinfunction "OUT4_22") (pintype "output"))
    )
    (net (code "105") (name "unconnected-(IC1-OUT7-Pad19)") (class "Default")
      (node (ref "IC1") (pin "19") (pinfunction "OUT7_19") (pintype "output"))
    )
    (net (code "106") (name "unconnected-(IC1-OUT9-Pad17)") (class "Default")
      (node (ref "IC1") (pin "17") (pinfunction "OUT9_17") (pintype "output"))
    )
    (net (code "107") (name "unconnected-(IC1-OUT12-Pad10)") (class "Default")
      (node (ref "IC1") (pin "10") (pinfunction "OUT12_10") (pintype "output"))
    )
    (net (code "108") (name "unconnected-(IC1-OUT15-Pad7)") (class "Default")
      (node (ref "IC1") (pin "7") (pinfunction "OUT15_7") (pintype "output"))
    )
    (net (code "109") (name "unconnected-(IC1-OUT17-Pad5)") (class "Default")
      (node (ref "IC1") (pin "5") (pinfunction "OUT17_5") (pintype "output"))
    )
    (net (code "110") (name "unconnected-(IC2-OUT0-Pad26)") (class "Default")
      (node (ref "IC2") (pin "26") (pinfunction "OUT0_26") (pintype "output"))
    )
    (net (code "111") (name "unconnected-(IC2-OUT3-Pad23)") (class "Default")
      (node (ref "IC2") (pin "23") (pinfunction "OUT3_23") (pintype "output"))
    )
    (net (code "112") (name "unconnected-(IC2-OUT5-Pad21)") (class "Default")
      (node (ref "IC2") (pin "21") (pinfunction "OUT5_21") (pintype "output"))
    )
    (net (code "113") (name "unconnected-(IC2-OUT8-Pad18)") (class "Default")
      (node (ref "IC2") (pin "18") (pinfunction "OUT8_18") (pintype "output"))
    )
    (net (code "114") (name "unconnected-(IC2-OUT11-Pad11)") (class "Default")
      (node (ref "IC2") (pin "11") (pinfunction "OUT11_11") (pintype "output"))
    )
    (net (code "115") (name "unconnected-(IC2-OUT13-Pad9)") (class "Default")
      (node (ref "IC2") (pin "9") (pinfunction "OUT13_9") (pintype "output"))
    )
    (net (code "116") (name "unconnected-(IC2-OUT16-Pad6)") (class "Default")
      (node (ref "IC2") (pin "6") (pinfunction "OUT16_6") (pintype "output"))
    )
    (net (code "117") (name "unconnected-(IC2-OUT19-Pad3)") (class "Default")
      (node (ref "IC2") (pin "3") (pinfunction "OUT19_3") (pintype "output"))
    )
    (net (code "118") (name "unconnected-(IC3-OUT1-Pad25)") (class "Default")
      (node (ref "IC3") (pin "25") (pinfunction "OUT1_25") (pintype "output"))
    )
    (net (code "119") (name "unconnected-(IC3-OUT4-Pad22)") (class "Default")
      (node (ref "IC3") (pin "22") (pinfunction "OUT4_22") (pintype "output"))
    )
    (net (code "120") (name "unconnected-(IC3-OUT7-Pad19)") (class "Default")
      (node (ref "IC3") (pin "19") (pinfunction "OUT7_19") (pintype "output"))
    )
    (net (code "121") (name "unconnected-(IC3-OUT9-Pad17)") (class "Default")
      (node (ref "IC3") (pin "17") (pinfunction "OUT9_17") (pintype "output"))
    )
    (net (code "122") (name "unconnected-(IC3-OUT12-Pad10)") (class "Default")
      (node (ref "IC3") (pin "10") (pinfunction "OUT12_10") (pintype "output"))
    )
    (net (code "123") (name "unconnected-(IC3-OUT15-Pad7)") (class "Default")
      (node (ref "IC3") (pin "7") (pinfunction "OUT15_7") (pintype "output"))
    )
    (net (code "124") (name "unconnected-(IC3-OUT17-Pad5)") (class "Default")
      (node (ref "IC3") (pin "5") (pinfunction "OUT17_5") (pintype "output"))
    )
    (net (code "125") (name "unconnected-(IC4-OUT0-Pad26)") (class "Default")
      (node (ref "IC4") (pin "26") (pinfunction "OUT0_26") (pintype "output"))
    )
    (net (code "126") (name "unconnected-(IC4-OUT3-Pad23)") (class "Default")
      (node (ref "IC4") (pin "23") (pinfunction "OUT3_23") (pintype "output"))
    )
    (net (code "127") (name "unconnected-(IC4-OUT5-Pad21)") (class "Default")
      (node (ref "IC4") (pin "21") (pinfunction "OUT5_21") (pintype "output"))
    )
    (net (code "128") (name "unconnected-(IC4-OUT8-Pad18)") (class "Default")
      (node (ref "IC4") (pin "18") (pinfunction "OUT8_18") (pintype "output"))
    )
    (net (code "129") (name "unconnected-(IC4-OUT11-Pad11)") (class "Default")
      (node (ref "IC4") (pin "11") (pinfunction "OUT11_11") (pintype "output"))
    )
    (net (code "130") (name "unconnected-(IC4-OUT13-Pad9)") (class "Default")
      (node (ref "IC4") (pin "9") (pinfunction "OUT13_9") (pintype "output"))
    )
    (net (code "131") (name "unconnected-(IC4-OUT16-Pad6)") (class "Default")
      (node (ref "IC4") (pin "6") (pinfunction "OUT16_6") (pintype "output"))
    )
    (net (code "132") (name "unconnected-(IC4-OUT19-Pad3)") (class "Default")
      (node (ref "IC4") (pin "3") (pinfunction "OUT19_3") (pintype "output"))
    )
    (net (code "133") (name "unconnected-(P1-PadRING_SW)") (class "Default")
      (node (ref "P1") (pin "RING_SW") (pinfunction "RING_SW_RING_SW") (pintype "bidirectional"))
    )
  )
)
